# Zaq_ISO.net
KiCad netlist of a schematic drawn in EAGLE
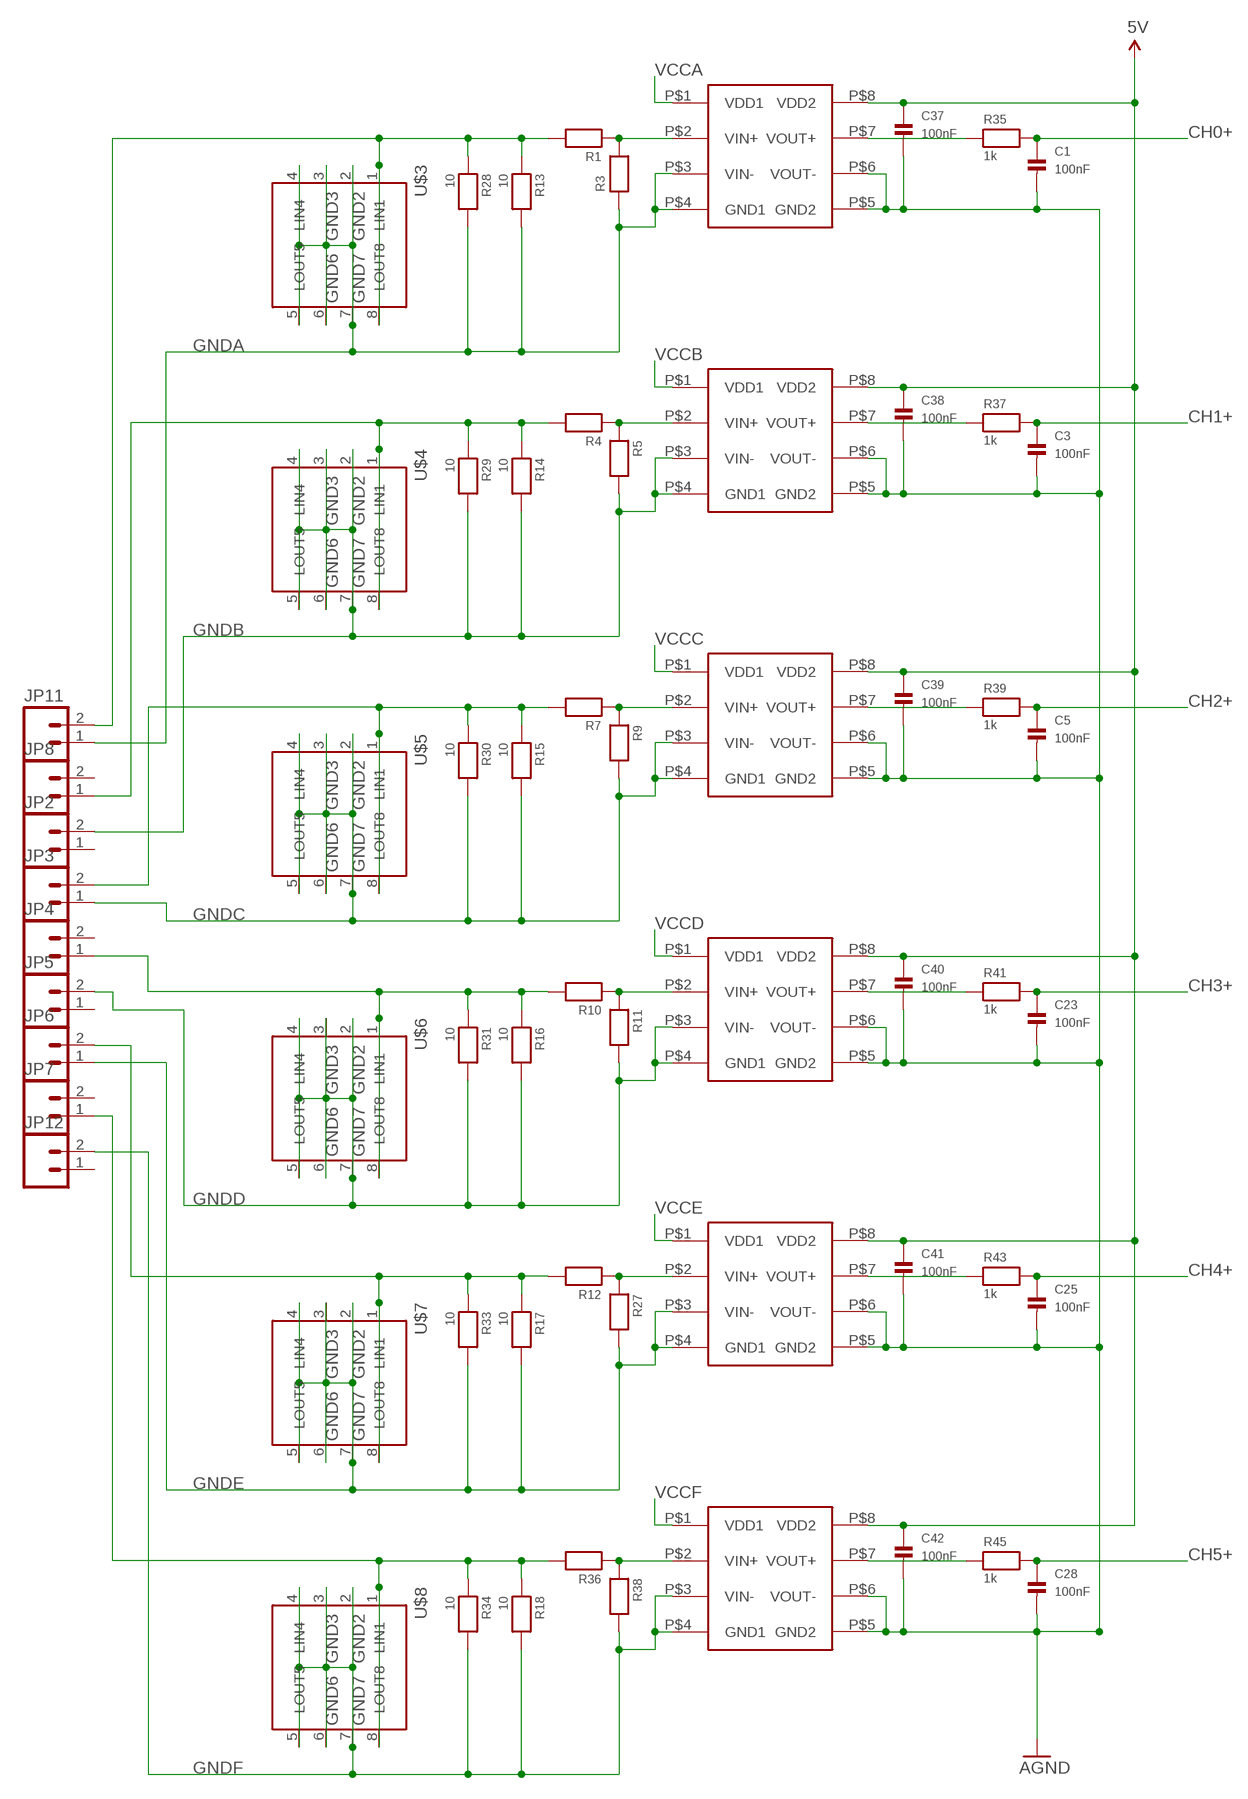
[diagram p0: schematic, sheet 1, part 1 of 2]
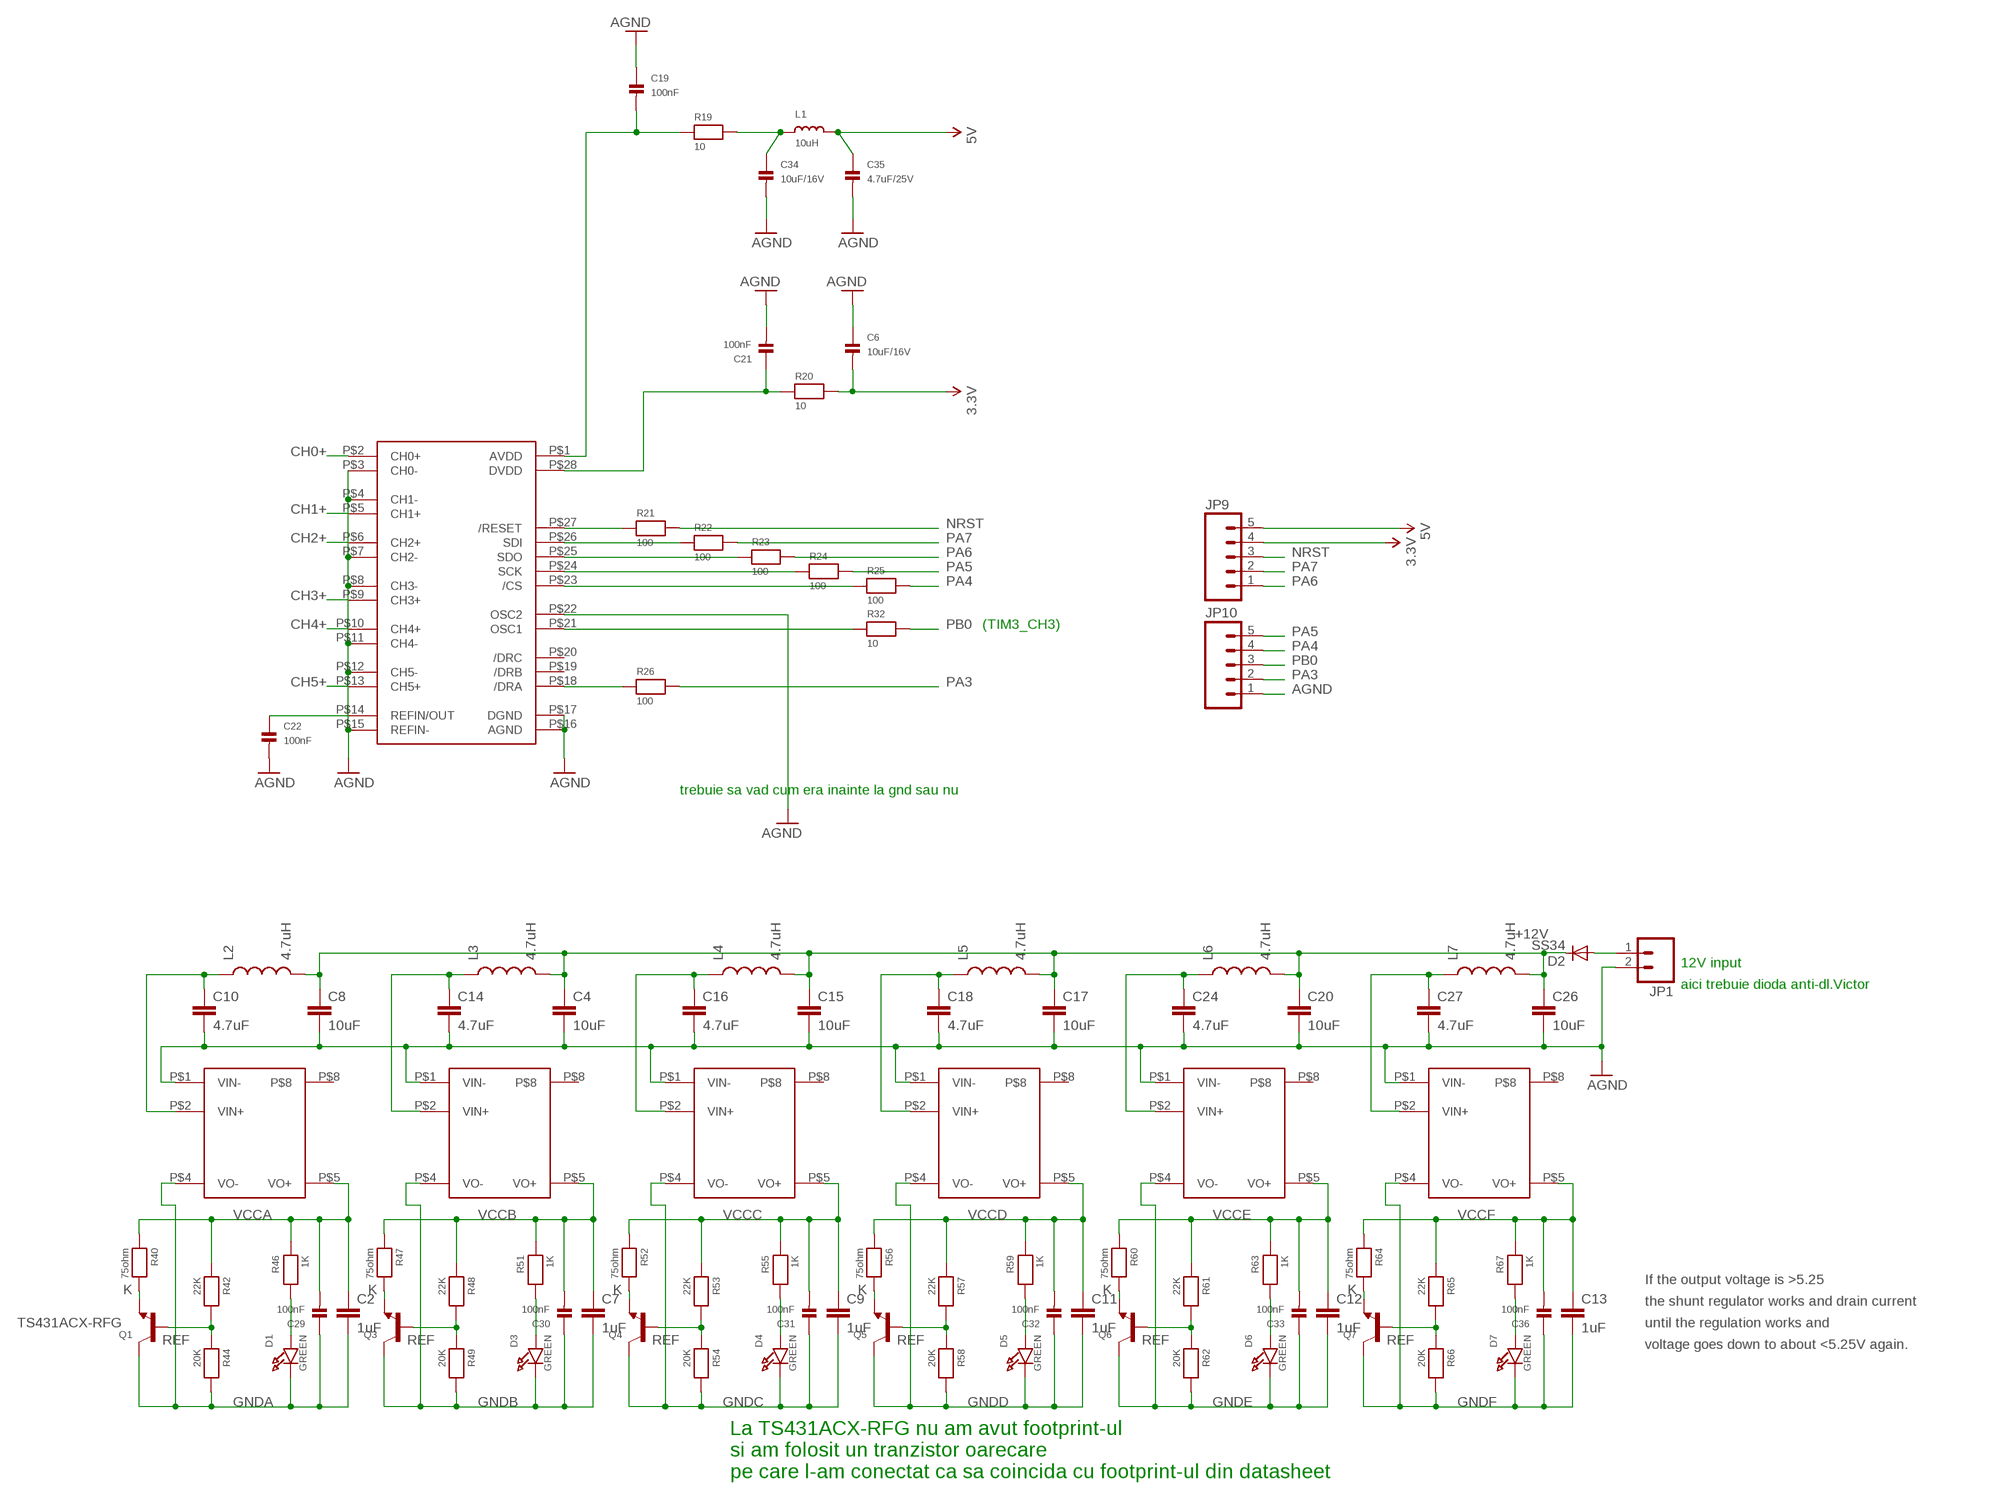
[diagram p1: schematic, sheet 1, part 2 of 2]

(export (version "E")
  (design (tool "Eeschema 10.0.6"))
  (components
    (comp (ref ".")
      (value "MCP3903")
      (footprint "eagle-import:SSOP-28")
      (libsource (lib "eagle-import") (part "MCP3903"))
    )
    (comp (ref "C1")
      (value "100nF")
      (footprint "eagle-import:_0805MP")
      (libsource (lib "eagle-import") (part "CAP_CERAMIC_0805MP"))
    )
    (comp (ref "C2")
      (value "1uF")
      (footprint "eagle-import:1206")
      (libsource (lib "eagle-import") (part "CAP1206"))
    )
    (comp (ref "C3")
      (value "100nF")
      (footprint "eagle-import:_0805MP")
      (libsource (lib "eagle-import") (part "CAP_CERAMIC_0805MP"))
    )
    (comp (ref "C4")
      (value "10uF")
      (footprint "eagle-import:1206")
      (libsource (lib "eagle-import") (part "CAP1206"))
    )
    (comp (ref "C5")
      (value "100nF")
      (footprint "eagle-import:_0805MP")
      (libsource (lib "eagle-import") (part "CAP_CERAMIC_0805MP"))
    )
    (comp (ref "C6")
      (value "10uF/16V")
      (footprint "eagle-import:_0805MP")
      (libsource (lib "eagle-import") (part "CAP_CERAMIC_0805MP"))
    )
    (comp (ref "C7")
      (value "1uF")
      (footprint "eagle-import:1206")
      (libsource (lib "eagle-import") (part "CAP1206"))
    )
    (comp (ref "C8")
      (value "10uF")
      (footprint "eagle-import:1206")
      (libsource (lib "eagle-import") (part "CAP1206"))
    )
    (comp (ref "C9")
      (value "1uF")
      (footprint "eagle-import:1206")
      (libsource (lib "eagle-import") (part "CAP1206"))
    )
    (comp (ref "C10")
      (value "4.7uF")
      (footprint "eagle-import:1206")
      (libsource (lib "eagle-import") (part "CAP1206"))
    )
    (comp (ref "C11")
      (value "1uF")
      (footprint "eagle-import:1206")
      (libsource (lib "eagle-import") (part "CAP1206"))
    )
    (comp (ref "C12")
      (value "1uF")
      (footprint "eagle-import:1206")
      (libsource (lib "eagle-import") (part "CAP1206"))
    )
    (comp (ref "C13")
      (value "1uF")
      (footprint "eagle-import:1206")
      (libsource (lib "eagle-import") (part "CAP1206"))
    )
    (comp (ref "C14")
      (value "4.7uF")
      (footprint "eagle-import:1206")
      (libsource (lib "eagle-import") (part "CAP1206"))
    )
    (comp (ref "C15")
      (value "10uF")
      (footprint "eagle-import:1206")
      (libsource (lib "eagle-import") (part "CAP1206"))
    )
    (comp (ref "C16")
      (value "4.7uF")
      (footprint "eagle-import:1206")
      (libsource (lib "eagle-import") (part "CAP1206"))
    )
    (comp (ref "C17")
      (value "10uF")
      (footprint "eagle-import:1206")
      (libsource (lib "eagle-import") (part "CAP1206"))
    )
    (comp (ref "C18")
      (value "4.7uF")
      (footprint "eagle-import:1206")
      (libsource (lib "eagle-import") (part "CAP1206"))
    )
    (comp (ref "C19")
      (value "100nF")
      (footprint "eagle-import:_0805MP")
      (libsource (lib "eagle-import") (part "CAP_CERAMIC_0805MP"))
    )
    (comp (ref "C20")
      (value "10uF")
      (footprint "eagle-import:1206")
      (libsource (lib "eagle-import") (part "CAP1206"))
    )
    (comp (ref "C21")
      (value "100nF")
      (footprint "eagle-import:_0805MP")
      (libsource (lib "eagle-import") (part "CAP_CERAMIC_0805MP"))
    )
    (comp (ref "C22")
      (value "100nF")
      (footprint "eagle-import:_0805MP")
      (libsource (lib "eagle-import") (part "CAP_CERAMIC_0805MP"))
    )
    (comp (ref "C23")
      (value "100nF")
      (footprint "eagle-import:_0805MP")
      (libsource (lib "eagle-import") (part "CAP_CERAMIC_0805MP"))
    )
    (comp (ref "C24")
      (value "4.7uF")
      (footprint "eagle-import:1206")
      (libsource (lib "eagle-import") (part "CAP1206"))
    )
    (comp (ref "C25")
      (value "100nF")
      (footprint "eagle-import:_0805MP")
      (libsource (lib "eagle-import") (part "CAP_CERAMIC_0805MP"))
    )
    (comp (ref "C26")
      (value "10uF")
      (footprint "eagle-import:1206")
      (libsource (lib "eagle-import") (part "CAP1206"))
    )
    (comp (ref "C27")
      (value "4.7uF")
      (footprint "eagle-import:1206")
      (libsource (lib "eagle-import") (part "CAP1206"))
    )
    (comp (ref "C28")
      (value "100nF")
      (footprint "eagle-import:_0805MP")
      (libsource (lib "eagle-import") (part "CAP_CERAMIC_0805MP"))
    )
    (comp (ref "C29")
      (value "100nF")
      (footprint "eagle-import:_0805MP")
      (libsource (lib "eagle-import") (part "CAP_CERAMIC_0805MP"))
    )
    (comp (ref "C30")
      (value "100nF")
      (footprint "eagle-import:_0805MP")
      (libsource (lib "eagle-import") (part "CAP_CERAMIC_0805MP"))
    )
    (comp (ref "C31")
      (value "100nF")
      (footprint "eagle-import:_0805MP")
      (libsource (lib "eagle-import") (part "CAP_CERAMIC_0805MP"))
    )
    (comp (ref "C32")
      (value "100nF")
      (footprint "eagle-import:_0805MP")
      (libsource (lib "eagle-import") (part "CAP_CERAMIC_0805MP"))
    )
    (comp (ref "C33")
      (value "100nF")
      (footprint "eagle-import:_0805MP")
      (libsource (lib "eagle-import") (part "CAP_CERAMIC_0805MP"))
    )
    (comp (ref "C34")
      (value "10uF/16V")
      (footprint "eagle-import:_0805MP")
      (libsource (lib "eagle-import") (part "CAP_CERAMIC_0805MP"))
    )
    (comp (ref "C35")
      (value "4.7uF/25V")
      (footprint "eagle-import:_0805MP")
      (libsource (lib "eagle-import") (part "CAP_CERAMIC_0805MP"))
    )
    (comp (ref "C36")
      (value "100nF")
      (footprint "eagle-import:_0805MP")
      (libsource (lib "eagle-import") (part "CAP_CERAMIC_0805MP"))
    )
    (comp (ref "C37")
      (value "100nF")
      (footprint "eagle-import:_0805MP")
      (libsource (lib "eagle-import") (part "CAP_CERAMIC_0805MP"))
    )
    (comp (ref "C38")
      (value "100nF")
      (footprint "eagle-import:_0805MP")
      (libsource (lib "eagle-import") (part "CAP_CERAMIC_0805MP"))
    )
    (comp (ref "C39")
      (value "100nF")
      (footprint "eagle-import:_0805MP")
      (libsource (lib "eagle-import") (part "CAP_CERAMIC_0805MP"))
    )
    (comp (ref "C40")
      (value "100nF")
      (footprint "eagle-import:_0805MP")
      (libsource (lib "eagle-import") (part "CAP_CERAMIC_0805MP"))
    )
    (comp (ref "C41")
      (value "100nF")
      (footprint "eagle-import:_0805MP")
      (libsource (lib "eagle-import") (part "CAP_CERAMIC_0805MP"))
    )
    (comp (ref "C42")
      (value "100nF")
      (footprint "eagle-import:_0805MP")
      (libsource (lib "eagle-import") (part "CAP_CERAMIC_0805MP"))
    )
    (comp (ref "D1")
      (value "GREEN")
      (footprint "eagle-import:CHIPLED_0805_NOOUTLINE")
      (libsource (lib "eagle-import") (part "LED0805_NOOUTLINE"))
    )
    (comp (ref "D2")
      (value "SS34")
      (footprint "eagle-import:SMC")
      (libsource (lib "eagle-import") (part "DIODE-SMC"))
    )
    (comp (ref "D3")
      (value "GREEN")
      (footprint "eagle-import:CHIPLED_0805_NOOUTLINE")
      (libsource (lib "eagle-import") (part "LED0805_NOOUTLINE"))
    )
    (comp (ref "D4")
      (value "GREEN")
      (footprint "eagle-import:CHIPLED_0805_NOOUTLINE")
      (libsource (lib "eagle-import") (part "LED0805_NOOUTLINE"))
    )
    (comp (ref "D5")
      (value "GREEN")
      (footprint "eagle-import:CHIPLED_0805_NOOUTLINE")
      (libsource (lib "eagle-import") (part "LED0805_NOOUTLINE"))
    )
    (comp (ref "D6")
      (value "GREEN")
      (footprint "eagle-import:CHIPLED_0805_NOOUTLINE")
      (libsource (lib "eagle-import") (part "LED0805_NOOUTLINE"))
    )
    (comp (ref "D7")
      (value "GREEN")
      (footprint "eagle-import:CHIPLED_0805_NOOUTLINE")
      (libsource (lib "eagle-import") (part "LED0805_NOOUTLINE"))
    )
    (comp (ref "JP1")
      (value "M025MM")
      (footprint "eagle-import:SCREWTERMINAL-5MM-2")
      (libsource (lib "eagle-import") (part "M025MM"))
    )
    (comp (ref "JP2")
      (value "M025MM")
      (footprint "eagle-import:SCREWTERMINAL-5MM-2")
      (libsource (lib "eagle-import") (part "M025MM"))
    )
    (comp (ref "JP3")
      (value "M025MM")
      (footprint "eagle-import:SCREWTERMINAL-5MM-2")
      (libsource (lib "eagle-import") (part "M025MM"))
    )
    (comp (ref "JP4")
      (value "M025MM")
      (footprint "eagle-import:SCREWTERMINAL-5MM-2")
      (libsource (lib "eagle-import") (part "M025MM"))
    )
    (comp (ref "JP5")
      (value "M025MM")
      (footprint "eagle-import:SCREWTERMINAL-5MM-2")
      (libsource (lib "eagle-import") (part "M025MM"))
    )
    (comp (ref "JP6")
      (value "M025MM")
      (footprint "eagle-import:SCREWTERMINAL-5MM-2")
      (libsource (lib "eagle-import") (part "M025MM"))
    )
    (comp (ref "JP7")
      (value "M025MM")
      (footprint "eagle-import:SCREWTERMINAL-5MM-2")
      (libsource (lib "eagle-import") (part "M025MM"))
    )
    (comp (ref "JP8")
      (value "M025MM")
      (footprint "eagle-import:SCREWTERMINAL-5MM-2")
      (libsource (lib "eagle-import") (part "M025MM"))
    )
    (comp (ref "JP9")
      (value "M05PTH_LONGPADS")
      (footprint "eagle-import:1X05_LONGPADS")
      (libsource (lib "eagle-import") (part "M05PTH_LONGPADS"))
    )
    (comp (ref "JP10")
      (value "M05PTH_LONGPADS")
      (footprint "eagle-import:1X05_LONGPADS")
      (libsource (lib "eagle-import") (part "M05PTH_LONGPADS"))
    )
    (comp (ref "JP11")
      (value "M025MM")
      (footprint "eagle-import:SCREWTERMINAL-5MM-2")
      (libsource (lib "eagle-import") (part "M025MM"))
    )
    (comp (ref "JP12")
      (value "M025MM")
      (footprint "eagle-import:SCREWTERMINAL-5MM-2")
      (libsource (lib "eagle-import") (part "M025MM"))
    )
    (comp (ref "L1")
      (value "10uH")
      (footprint "eagle-import:_0805MP")
      (libsource (lib "eagle-import") (part "INDUCTOR_0805MP"))
    )
    (comp (ref "L2")
      (value "4.7uH")
      (footprint "eagle-import:1210")
      (libsource (lib "eagle-import") (part "INDUCTOR1210"))
    )
    (comp (ref "L3")
      (value "4.7uH")
      (footprint "eagle-import:1210")
      (libsource (lib "eagle-import") (part "INDUCTOR1210"))
    )
    (comp (ref "L4")
      (value "4.7uH")
      (footprint "eagle-import:1210")
      (libsource (lib "eagle-import") (part "INDUCTOR1210"))
    )
    (comp (ref "L5")
      (value "4.7uH")
      (footprint "eagle-import:1210")
      (libsource (lib "eagle-import") (part "INDUCTOR1210"))
    )
    (comp (ref "L6")
      (value "4.7uH")
      (footprint "eagle-import:1210")
      (libsource (lib "eagle-import") (part "INDUCTOR1210"))
    )
    (comp (ref "L7")
      (value "4.7uH")
      (footprint "eagle-import:1210")
      (libsource (lib "eagle-import") (part "INDUCTOR1210"))
    )
    (comp (ref "Q1")
      (value "TRANSISTOR_NPNWAVE")
      (footprint "eagle-import:SOT23-W")
      (libsource (lib "eagle-import") (part "TRANSISTOR_NPNWAVE"))
    )
    (comp (ref "Q3")
      (value "TRANSISTOR_NPNWAVE")
      (footprint "eagle-import:SOT23-W")
      (libsource (lib "eagle-import") (part "TRANSISTOR_NPNWAVE"))
    )
    (comp (ref "Q4")
      (value "TRANSISTOR_NPNWAVE")
      (footprint "eagle-import:SOT23-W")
      (libsource (lib "eagle-import") (part "TRANSISTOR_NPNWAVE"))
    )
    (comp (ref "Q5")
      (value "TRANSISTOR_NPNWAVE")
      (footprint "eagle-import:SOT23-W")
      (libsource (lib "eagle-import") (part "TRANSISTOR_NPNWAVE"))
    )
    (comp (ref "Q6")
      (value "TRANSISTOR_NPNWAVE")
      (footprint "eagle-import:SOT23-W")
      (libsource (lib "eagle-import") (part "TRANSISTOR_NPNWAVE"))
    )
    (comp (ref "Q7")
      (value "TRANSISTOR_NPNWAVE")
      (footprint "eagle-import:SOT23-W")
      (libsource (lib "eagle-import") (part "TRANSISTOR_NPNWAVE"))
    )
    (comp (ref "R1")
      (value "RESISTOR_0805MP")
      (footprint "eagle-import:_0805MP")
      (libsource (lib "eagle-import") (part "RESISTOR_0805MP"))
    )
    (comp (ref "R3")
      (value "RESISTOR_0805MP")
      (footprint "eagle-import:_0805MP")
      (libsource (lib "eagle-import") (part "RESISTOR_0805MP"))
    )
    (comp (ref "R4")
      (value "RESISTOR_0805MP")
      (footprint "eagle-import:_0805MP")
      (libsource (lib "eagle-import") (part "RESISTOR_0805MP"))
    )
    (comp (ref "R5")
      (value "RESISTOR_0805MP")
      (footprint "eagle-import:_0805MP")
      (libsource (lib "eagle-import") (part "RESISTOR_0805MP"))
    )
    (comp (ref "R7")
      (value "RESISTOR_0805MP")
      (footprint "eagle-import:_0805MP")
      (libsource (lib "eagle-import") (part "RESISTOR_0805MP"))
    )
    (comp (ref "R9")
      (value "RESISTOR_0805MP")
      (footprint "eagle-import:_0805MP")
      (libsource (lib "eagle-import") (part "RESISTOR_0805MP"))
    )
    (comp (ref "R10")
      (value "RESISTOR_0805MP")
      (footprint "eagle-import:_0805MP")
      (libsource (lib "eagle-import") (part "RESISTOR_0805MP"))
    )
    (comp (ref "R11")
      (value "RESISTOR_0805MP")
      (footprint "eagle-import:_0805MP")
      (libsource (lib "eagle-import") (part "RESISTOR_0805MP"))
    )
    (comp (ref "R12")
      (value "RESISTOR_0805MP")
      (footprint "eagle-import:_0805MP")
      (libsource (lib "eagle-import") (part "RESISTOR_0805MP"))
    )
    (comp (ref "R13")
      (value "10")
      (footprint "eagle-import:1206")
      (libsource (lib "eagle-import") (part "RESISTOR1206"))
    )
    (comp (ref "R14")
      (value "10")
      (footprint "eagle-import:1206")
      (libsource (lib "eagle-import") (part "RESISTOR1206"))
    )
    (comp (ref "R15")
      (value "10")
      (footprint "eagle-import:1206")
      (libsource (lib "eagle-import") (part "RESISTOR1206"))
    )
    (comp (ref "R16")
      (value "10")
      (footprint "eagle-import:1206")
      (libsource (lib "eagle-import") (part "RESISTOR1206"))
    )
    (comp (ref "R17")
      (value "10")
      (footprint "eagle-import:1206")
      (libsource (lib "eagle-import") (part "RESISTOR1206"))
    )
    (comp (ref "R18")
      (value "10")
      (footprint "eagle-import:1206")
      (libsource (lib "eagle-import") (part "RESISTOR1206"))
    )
    (comp (ref "R19")
      (value "10")
      (footprint "eagle-import:_0805MP")
      (libsource (lib "eagle-import") (part "RESISTOR_0805MP"))
    )
    (comp (ref "R20")
      (value "10")
      (footprint "eagle-import:_0805MP")
      (libsource (lib "eagle-import") (part "RESISTOR_0805MP"))
    )
    (comp (ref "R21")
      (value "100")
      (footprint "eagle-import:_0805MP")
      (libsource (lib "eagle-import") (part "RESISTOR_0805MP"))
    )
    (comp (ref "R22")
      (value "100")
      (footprint "eagle-import:_0805MP")
      (libsource (lib "eagle-import") (part "RESISTOR_0805MP"))
    )
    (comp (ref "R23")
      (value "100")
      (footprint "eagle-import:_0805MP")
      (libsource (lib "eagle-import") (part "RESISTOR_0805MP"))
    )
    (comp (ref "R24")
      (value "100")
      (footprint "eagle-import:_0805MP")
      (libsource (lib "eagle-import") (part "RESISTOR_0805MP"))
    )
    (comp (ref "R25")
      (value "100")
      (footprint "eagle-import:_0805MP")
      (libsource (lib "eagle-import") (part "RESISTOR_0805MP"))
    )
    (comp (ref "R26")
      (value "100")
      (footprint "eagle-import:_0805MP")
      (libsource (lib "eagle-import") (part "RESISTOR_0805MP"))
    )
    (comp (ref "R27")
      (value "RESISTOR_0805MP")
      (footprint "eagle-import:_0805MP")
      (libsource (lib "eagle-import") (part "RESISTOR_0805MP"))
    )
    (comp (ref "R28")
      (value "10")
      (footprint "eagle-import:1206")
      (libsource (lib "eagle-import") (part "RESISTOR1206"))
    )
    (comp (ref "R29")
      (value "10")
      (footprint "eagle-import:1206")
      (libsource (lib "eagle-import") (part "RESISTOR1206"))
    )
    (comp (ref "R30")
      (value "10")
      (footprint "eagle-import:1206")
      (libsource (lib "eagle-import") (part "RESISTOR1206"))
    )
    (comp (ref "R31")
      (value "10")
      (footprint "eagle-import:1206")
      (libsource (lib "eagle-import") (part "RESISTOR1206"))
    )
    (comp (ref "R32")
      (value "10")
      (footprint "eagle-import:_0805MP")
      (libsource (lib "eagle-import") (part "RESISTOR_0805MP"))
    )
    (comp (ref "R33")
      (value "10")
      (footprint "eagle-import:1206")
      (libsource (lib "eagle-import") (part "RESISTOR1206"))
    )
    (comp (ref "R34")
      (value "10")
      (footprint "eagle-import:1206")
      (libsource (lib "eagle-import") (part "RESISTOR1206"))
    )
    (comp (ref "R35")
      (value "1k")
      (footprint "eagle-import:_0805MP")
      (libsource (lib "eagle-import") (part "RESISTOR_0805MP"))
    )
    (comp (ref "R36")
      (value "RESISTOR_0805MP")
      (footprint "eagle-import:_0805MP")
      (libsource (lib "eagle-import") (part "RESISTOR_0805MP"))
    )
    (comp (ref "R37")
      (value "1k")
      (footprint "eagle-import:_0805MP")
      (libsource (lib "eagle-import") (part "RESISTOR_0805MP"))
    )
    (comp (ref "R38")
      (value "RESISTOR_0805MP")
      (footprint "eagle-import:_0805MP")
      (libsource (lib "eagle-import") (part "RESISTOR_0805MP"))
    )
    (comp (ref "R39")
      (value "1k")
      (footprint "eagle-import:_0805MP")
      (libsource (lib "eagle-import") (part "RESISTOR_0805MP"))
    )
    (comp (ref "R40")
      (value "75ohm")
      (footprint "eagle-import:_0805MP")
      (libsource (lib "eagle-import") (part "RESISTOR_0805MP"))
    )
    (comp (ref "R41")
      (value "1k")
      (footprint "eagle-import:_0805MP")
      (libsource (lib "eagle-import") (part "RESISTOR_0805MP"))
    )
    (comp (ref "R42")
      (value "22K")
      (footprint "eagle-import:_0805MP")
      (libsource (lib "eagle-import") (part "RESISTOR_0805MP"))
    )
    (comp (ref "R43")
      (value "1k")
      (footprint "eagle-import:_0805MP")
      (libsource (lib "eagle-import") (part "RESISTOR_0805MP"))
    )
    (comp (ref "R44")
      (value "20K")
      (footprint "eagle-import:_0805MP")
      (libsource (lib "eagle-import") (part "RESISTOR_0805MP"))
    )
    (comp (ref "R45")
      (value "1k")
      (footprint "eagle-import:_0805MP")
      (libsource (lib "eagle-import") (part "RESISTOR_0805MP"))
    )
    (comp (ref "R46")
      (value "1K")
      (footprint "eagle-import:_0805MP")
      (libsource (lib "eagle-import") (part "RESISTOR_0805MP"))
    )
    (comp (ref "R47")
      (value "75ohm")
      (footprint "eagle-import:_0805MP")
      (libsource (lib "eagle-import") (part "RESISTOR_0805MP"))
    )
    (comp (ref "R48")
      (value "22K")
      (footprint "eagle-import:_0805MP")
      (libsource (lib "eagle-import") (part "RESISTOR_0805MP"))
    )
    (comp (ref "R49")
      (value "20K")
      (footprint "eagle-import:_0805MP")
      (libsource (lib "eagle-import") (part "RESISTOR_0805MP"))
    )
    (comp (ref "R51")
      (value "1K")
      (footprint "eagle-import:_0805MP")
      (libsource (lib "eagle-import") (part "RESISTOR_0805MP"))
    )
    (comp (ref "R52")
      (value "75ohm")
      (footprint "eagle-import:_0805MP")
      (libsource (lib "eagle-import") (part "RESISTOR_0805MP"))
    )
    (comp (ref "R53")
      (value "22K")
      (footprint "eagle-import:_0805MP")
      (libsource (lib "eagle-import") (part "RESISTOR_0805MP"))
    )
    (comp (ref "R54")
      (value "20K")
      (footprint "eagle-import:_0805MP")
      (libsource (lib "eagle-import") (part "RESISTOR_0805MP"))
    )
    (comp (ref "R55")
      (value "1K")
      (footprint "eagle-import:_0805MP")
      (libsource (lib "eagle-import") (part "RESISTOR_0805MP"))
    )
    (comp (ref "R56")
      (value "75ohm")
      (footprint "eagle-import:_0805MP")
      (libsource (lib "eagle-import") (part "RESISTOR_0805MP"))
    )
    (comp (ref "R57")
      (value "22K")
      (footprint "eagle-import:_0805MP")
      (libsource (lib "eagle-import") (part "RESISTOR_0805MP"))
    )
    (comp (ref "R58")
      (value "20K")
      (footprint "eagle-import:_0805MP")
      (libsource (lib "eagle-import") (part "RESISTOR_0805MP"))
    )
    (comp (ref "R59")
      (value "1K")
      (footprint "eagle-import:_0805MP")
      (libsource (lib "eagle-import") (part "RESISTOR_0805MP"))
    )
    (comp (ref "R60")
      (value "75ohm")
      (footprint "eagle-import:_0805MP")
      (libsource (lib "eagle-import") (part "RESISTOR_0805MP"))
    )
    (comp (ref "R61")
      (value "22K")
      (footprint "eagle-import:_0805MP")
      (libsource (lib "eagle-import") (part "RESISTOR_0805MP"))
    )
    (comp (ref "R62")
      (value "20K")
      (footprint "eagle-import:_0805MP")
      (libsource (lib "eagle-import") (part "RESISTOR_0805MP"))
    )
    (comp (ref "R63")
      (value "1K")
      (footprint "eagle-import:_0805MP")
      (libsource (lib "eagle-import") (part "RESISTOR_0805MP"))
    )
    (comp (ref "R64")
      (value "75ohm")
      (footprint "eagle-import:_0805MP")
      (libsource (lib "eagle-import") (part "RESISTOR_0805MP"))
    )
    (comp (ref "R65")
      (value "22K")
      (footprint "eagle-import:_0805MP")
      (libsource (lib "eagle-import") (part "RESISTOR_0805MP"))
    )
    (comp (ref "R66")
      (value "20K")
      (footprint "eagle-import:_0805MP")
      (libsource (lib "eagle-import") (part "RESISTOR_0805MP"))
    )
    (comp (ref "R67")
      (value "1K")
      (footprint "eagle-import:_0805MP")
      (libsource (lib "eagle-import") (part "RESISTOR_0805MP"))
    )
    (comp (ref "U$2")
      (value "AMC1200SDUB")
      (footprint "eagle-import:SOP")
      (libsource (lib "eagle-import") (part "AMC1200SDUB"))
    )
    (comp (ref "U$3")
      (value "LC03_3V3")
      (footprint "eagle-import:SO8")
      (libsource (lib "eagle-import") (part "LC03_3V3"))
    )
    (comp (ref "U$4")
      (value "LC03_3V3")
      (footprint "eagle-import:SO8")
      (libsource (lib "eagle-import") (part "LC03_3V3"))
    )
    (comp (ref "U$5")
      (value "LC03_3V3")
      (footprint "eagle-import:SO8")
      (libsource (lib "eagle-import") (part "LC03_3V3"))
    )
    (comp (ref "U$6")
      (value "LC03_3V3")
      (footprint "eagle-import:SO8")
      (libsource (lib "eagle-import") (part "LC03_3V3"))
    )
    (comp (ref "U$7")
      (value "LC03_3V3")
      (footprint "eagle-import:SO8")
      (libsource (lib "eagle-import") (part "LC03_3V3"))
    )
    (comp (ref "U$8")
      (value "LC03_3V3")
      (footprint "eagle-import:SO8")
      (libsource (lib "eagle-import") (part "LC03_3V3"))
    )
    (comp (ref "U$9")
      (value "AMC1200SDUB")
      (footprint "eagle-import:SOP")
      (libsource (lib "eagle-import") (part "AMC1200SDUB"))
    )
    (comp (ref "U$12")
      (value "AMC1200SDUB")
      (footprint "eagle-import:SOP")
      (libsource (lib "eagle-import") (part "AMC1200SDUB"))
    )
    (comp (ref "U$16")
      (value "AMC1200SDUB")
      (footprint "eagle-import:SOP")
      (libsource (lib "eagle-import") (part "AMC1200SDUB"))
    )
    (comp (ref "U$17")
      (value "AM1LS-NJZ")
      (footprint "eagle-import:AM1LS-JZ")
      (libsource (lib "eagle-import") (part "AM1LS-NJZ"))
    )
    (comp (ref "U$18")
      (value "AMC1200SDUB")
      (footprint "eagle-import:SOP")
      (libsource (lib "eagle-import") (part "AMC1200SDUB"))
    )
    (comp (ref "U$19")
      (value "AMC1200SDUB")
      (footprint "eagle-import:SOP")
      (libsource (lib "eagle-import") (part "AMC1200SDUB"))
    )
    (comp (ref "U$20")
      (value "AM1LS-NJZ")
      (footprint "eagle-import:AM1LS-JZ")
      (libsource (lib "eagle-import") (part "AM1LS-NJZ"))
    )
    (comp (ref "U$22")
      (value "AM1LS-NJZ")
      (footprint "eagle-import:AM1LS-JZ")
      (libsource (lib "eagle-import") (part "AM1LS-NJZ"))
    )
    (comp (ref "U$23")
      (value "AM1LS-NJZ")
      (footprint "eagle-import:AM1LS-JZ")
      (libsource (lib "eagle-import") (part "AM1LS-NJZ"))
    )
    (comp (ref "U$24")
      (value "AM1LS-NJZ")
      (footprint "eagle-import:AM1LS-JZ")
      (libsource (lib "eagle-import") (part "AM1LS-NJZ"))
    )
    (comp (ref "U$25")
      (value "AM1LS-NJZ")
      (footprint "eagle-import:AM1LS-JZ")
      (libsource (lib "eagle-import") (part "AM1LS-NJZ"))
    )
  )
  (nets
    (net (code "1") (name "/+12V") (class "Default")
      (node (ref "C15") (pin "1") (pinfunction "1_1") (pintype "passive"))
      (node (ref "C17") (pin "1") (pinfunction "1_1") (pintype "passive"))
      (node (ref "C20") (pin "1") (pinfunction "1_1") (pintype "passive"))
      (node (ref "C26") (pin "1") (pinfunction "1_1") (pintype "passive"))
      (node (ref "C4") (pin "1") (pinfunction "1_1") (pintype "passive"))
      (node (ref "C8") (pin "1") (pinfunction "1_1") (pintype "passive"))
      (node (ref "D2") (pin "C") (pinfunction "C_C") (pintype "passive"))
      (node (ref "L2") (pin "2") (pinfunction "2_2") (pintype "passive"))
      (node (ref "L3") (pin "2") (pinfunction "2_2") (pintype "passive"))
      (node (ref "L4") (pin "2") (pinfunction "2_2") (pintype "passive"))
      (node (ref "L5") (pin "2") (pinfunction "2_2") (pintype "passive"))
      (node (ref "L6") (pin "2") (pinfunction "2_2") (pintype "passive"))
      (node (ref "L7") (pin "2") (pinfunction "2_2") (pintype "passive"))
    )
    (net (code "2") (name "/CH0+") (class "Default")
      (node (ref ".") (pin "P$2") (pinfunction "CH0+_P$2") (pintype "bidirectional"))
      (node (ref "C1") (pin "1") (pinfunction "P$1_1") (pintype "passive"))
      (node (ref "R35") (pin "2") (pinfunction "2_2") (pintype "passive"))
    )
    (net (code "3") (name "/CH1+") (class "Default")
      (node (ref ".") (pin "P$5") (pinfunction "CH1+_P$5") (pintype "bidirectional"))
      (node (ref "C3") (pin "1") (pinfunction "P$1_1") (pintype "passive"))
      (node (ref "R37") (pin "2") (pinfunction "2_2") (pintype "passive"))
    )
    (net (code "4") (name "/CH2+") (class "Default")
      (node (ref ".") (pin "P$6") (pinfunction "CH2+_P$6") (pintype "bidirectional"))
      (node (ref "C5") (pin "1") (pinfunction "P$1_1") (pintype "passive"))
      (node (ref "R39") (pin "2") (pinfunction "2_2") (pintype "passive"))
    )
    (net (code "5") (name "/CH3+") (class "Default")
      (node (ref ".") (pin "P$9") (pinfunction "CH3+_P$9") (pintype "bidirectional"))
      (node (ref "C23") (pin "1") (pinfunction "P$1_1") (pintype "passive"))
      (node (ref "R41") (pin "2") (pinfunction "2_2") (pintype "passive"))
    )
    (net (code "6") (name "/CH4+") (class "Default")
      (node (ref ".") (pin "P$10") (pinfunction "CH4+_P$10") (pintype "bidirectional"))
      (node (ref "C25") (pin "1") (pinfunction "P$1_1") (pintype "passive"))
      (node (ref "R43") (pin "2") (pinfunction "2_2") (pintype "passive"))
    )
    (net (code "7") (name "/CH5+") (class "Default")
      (node (ref ".") (pin "P$13") (pinfunction "CH5+_P$13") (pintype "bidirectional"))
      (node (ref "C28") (pin "1") (pinfunction "P$1_1") (pintype "passive"))
      (node (ref "R45") (pin "2") (pinfunction "2_2") (pintype "passive"))
    )
    (net (code "8") (name "/GNDA") (class "Default")
      (node (ref "C2") (pin "2") (pinfunction "2_2") (pintype "passive"))
      (node (ref "C29") (pin "1") (pinfunction "P$1_1") (pintype "passive"))
      (node (ref "D1") (pin "C") (pinfunction "C_C") (pintype "passive"))
      (node (ref "JP11") (pin "1") (pinfunction "1_1") (pintype "passive"))
      (node (ref "Q1") (pin "3") (pinfunction "C_3") (pintype "passive"))
      (node (ref "R13") (pin "2") (pinfunction "2_2") (pintype "passive"))
      (node (ref "R28") (pin "2") (pinfunction "2_2") (pintype "passive"))
      (node (ref "R3") (pin "1") (pinfunction "1_1") (pintype "passive"))
      (node (ref "R44") (pin "2") (pinfunction "2_2") (pintype "passive"))
      (node (ref "U$17") (pin "P$4") (pinfunction "VO-_P$4") (pintype "power_in"))
      (node (ref "U$2") (pin "P$3") (pinfunction "VIN-_P$3") (pintype "bidirectional"))
      (node (ref "U$2") (pin "P$4") (pinfunction "GND1_P$4") (pintype "power_in"))
      (node (ref "U$3") (pin "2") (pinfunction "GND_2_2") (pintype "power_in"))
      (node (ref "U$3") (pin "3") (pinfunction "GND_3_3") (pintype "power_in"))
      (node (ref "U$3") (pin "4") (pinfunction "LIN4_4") (pintype "input"))
      (node (ref "U$3") (pin "5") (pinfunction "LOUT5_5") (pintype "input"))
      (node (ref "U$3") (pin "6") (pinfunction "GND_6_6") (pintype "power_in"))
      (node (ref "U$3") (pin "7") (pinfunction "GND_7_7") (pintype "power_in"))
    )
    (net (code "9") (name "/GNDB") (class "Default")
      (node (ref "C30") (pin "1") (pinfunction "P$1_1") (pintype "passive"))
      (node (ref "C7") (pin "2") (pinfunction "2_2") (pintype "passive"))
      (node (ref "D3") (pin "C") (pinfunction "C_C") (pintype "passive"))
      (node (ref "JP2") (pin "2") (pinfunction "2_2") (pintype "passive"))
      (node (ref "Q3") (pin "3") (pinfunction "C_3") (pintype "passive"))
      (node (ref "R14") (pin "2") (pinfunction "2_2") (pintype "passive"))
      (node (ref "R29") (pin "2") (pinfunction "2_2") (pintype "passive"))
      (node (ref "R49") (pin "2") (pinfunction "2_2") (pintype "passive"))
      (node (ref "R5") (pin "2") (pinfunction "2_2") (pintype "passive"))
      (node (ref "U$20") (pin "P$4") (pinfunction "VO-_P$4") (pintype "power_in"))
      (node (ref "U$4") (pin "2") (pinfunction "GND_2_2") (pintype "power_in"))
      (node (ref "U$4") (pin "3") (pinfunction "GND_3_3") (pintype "power_in"))
      (node (ref "U$4") (pin "4") (pinfunction "LIN4_4") (pintype "input"))
      (node (ref "U$4") (pin "5") (pinfunction "LOUT5_5") (pintype "input"))
      (node (ref "U$4") (pin "6") (pinfunction "GND_6_6") (pintype "power_in"))
      (node (ref "U$4") (pin "7") (pinfunction "GND_7_7") (pintype "power_in"))
      (node (ref "U$9") (pin "P$3") (pinfunction "VIN-_P$3") (pintype "bidirectional"))
      (node (ref "U$9") (pin "P$4") (pinfunction "GND1_P$4") (pintype "power_in"))
    )
    (net (code "10") (name "/GNDC") (class "Default")
      (node (ref "C31") (pin "1") (pinfunction "P$1_1") (pintype "passive"))
      (node (ref "C9") (pin "2") (pinfunction "2_2") (pintype "passive"))
      (node (ref "D4") (pin "C") (pinfunction "C_C") (pintype "passive"))
      (node (ref "JP3") (pin "1") (pinfunction "1_1") (pintype "passive"))
      (node (ref "Q4") (pin "3") (pinfunction "C_3") (pintype "passive"))
      (node (ref "R15") (pin "2") (pinfunction "2_2") (pintype "passive"))
      (node (ref "R30") (pin "2") (pinfunction "2_2") (pintype "passive"))
      (node (ref "R54") (pin "2") (pinfunction "2_2") (pintype "passive"))
      (node (ref "R9") (pin "2") (pinfunction "2_2") (pintype "passive"))
      (node (ref "U$12") (pin "P$3") (pinfunction "VIN-_P$3") (pintype "bidirectional"))
      (node (ref "U$12") (pin "P$4") (pinfunction "GND1_P$4") (pintype "power_in"))
      (node (ref "U$22") (pin "P$4") (pinfunction "VO-_P$4") (pintype "power_in"))
      (node (ref "U$5") (pin "2") (pinfunction "GND_2_2") (pintype "power_in"))
      (node (ref "U$5") (pin "3") (pinfunction "GND_3_3") (pintype "power_in"))
      (node (ref "U$5") (pin "4") (pinfunction "LIN4_4") (pintype "input"))
      (node (ref "U$5") (pin "5") (pinfunction "LOUT5_5") (pintype "input"))
      (node (ref "U$5") (pin "6") (pinfunction "GND_6_6") (pintype "power_in"))
      (node (ref "U$5") (pin "7") (pinfunction "GND_7_7") (pintype "power_in"))
    )
    (net (code "11") (name "/GNDD") (class "Default")
      (node (ref "C11") (pin "2") (pinfunction "2_2") (pintype "passive"))
      (node (ref "C32") (pin "1") (pinfunction "P$1_1") (pintype "passive"))
      (node (ref "D5") (pin "C") (pinfunction "C_C") (pintype "passive"))
      (node (ref "JP5") (pin "2") (pinfunction "2_2") (pintype "passive"))
      (node (ref "Q5") (pin "3") (pinfunction "C_3") (pintype "passive"))
      (node (ref "R11") (pin "2") (pinfunction "2_2") (pintype "passive"))
      (node (ref "R16") (pin "2") (pinfunction "2_2") (pintype "passive"))
      (node (ref "R31") (pin "2") (pinfunction "2_2") (pintype "passive"))
      (node (ref "R58") (pin "2") (pinfunction "2_2") (pintype "passive"))
      (node (ref "U$16") (pin "P$3") (pinfunction "VIN-_P$3") (pintype "bidirectional"))
      (node (ref "U$16") (pin "P$4") (pinfunction "GND1_P$4") (pintype "power_in"))
      (node (ref "U$23") (pin "P$4") (pinfunction "VO-_P$4") (pintype "power_in"))
      (node (ref "U$6") (pin "2") (pinfunction "GND_2_2") (pintype "power_in"))
      (node (ref "U$6") (pin "3") (pinfunction "GND_3_3") (pintype "power_in"))
      (node (ref "U$6") (pin "4") (pinfunction "LIN4_4") (pintype "input"))
      (node (ref "U$6") (pin "5") (pinfunction "LOUT5_5") (pintype "input"))
      (node (ref "U$6") (pin "6") (pinfunction "GND_6_6") (pintype "power_in"))
      (node (ref "U$6") (pin "7") (pinfunction "GND_7_7") (pintype "power_in"))
    )
    (net (code "12") (name "/GNDE") (class "Default")
      (node (ref "C12") (pin "2") (pinfunction "2_2") (pintype "passive"))
      (node (ref "C33") (pin "1") (pinfunction "P$1_1") (pintype "passive"))
      (node (ref "D6") (pin "C") (pinfunction "C_C") (pintype "passive"))
      (node (ref "JP6") (pin "1") (pinfunction "1_1") (pintype "passive"))
      (node (ref "Q6") (pin "3") (pinfunction "C_3") (pintype "passive"))
      (node (ref "R17") (pin "2") (pinfunction "2_2") (pintype "passive"))
      (node (ref "R27") (pin "2") (pinfunction "2_2") (pintype "passive"))
      (node (ref "R33") (pin "2") (pinfunction "2_2") (pintype "passive"))
      (node (ref "R62") (pin "2") (pinfunction "2_2") (pintype "passive"))
      (node (ref "U$18") (pin "P$3") (pinfunction "VIN-_P$3") (pintype "bidirectional"))
      (node (ref "U$18") (pin "P$4") (pinfunction "GND1_P$4") (pintype "power_in"))
      (node (ref "U$24") (pin "P$4") (pinfunction "VO-_P$4") (pintype "power_in"))
      (node (ref "U$7") (pin "2") (pinfunction "GND_2_2") (pintype "power_in"))
      (node (ref "U$7") (pin "3") (pinfunction "GND_3_3") (pintype "power_in"))
      (node (ref "U$7") (pin "4") (pinfunction "LIN4_4") (pintype "input"))
      (node (ref "U$7") (pin "5") (pinfunction "LOUT5_5") (pintype "input"))
      (node (ref "U$7") (pin "6") (pinfunction "GND_6_6") (pintype "power_in"))
      (node (ref "U$7") (pin "7") (pinfunction "GND_7_7") (pintype "power_in"))
    )
    (net (code "13") (name "/GNDF") (class "Default")
      (node (ref "C13") (pin "2") (pinfunction "2_2") (pintype "passive"))
      (node (ref "C36") (pin "1") (pinfunction "P$1_1") (pintype "passive"))
      (node (ref "D7") (pin "C") (pinfunction "C_C") (pintype "passive"))
      (node (ref "JP12") (pin "2") (pinfunction "2_2") (pintype "passive"))
      (node (ref "Q7") (pin "3") (pinfunction "C_3") (pintype "passive"))
      (node (ref "R18") (pin "2") (pinfunction "2_2") (pintype "passive"))
      (node (ref "R34") (pin "2") (pinfunction "2_2") (pintype "passive"))
      (node (ref "R38") (pin "2") (pinfunction "2_2") (pintype "passive"))
      (node (ref "R66") (pin "2") (pinfunction "2_2") (pintype "passive"))
      (node (ref "U$19") (pin "P$3") (pinfunction "VIN-_P$3") (pintype "bidirectional"))
      (node (ref "U$19") (pin "P$4") (pinfunction "GND1_P$4") (pintype "power_in"))
      (node (ref "U$25") (pin "P$4") (pinfunction "VO-_P$4") (pintype "power_in"))
      (node (ref "U$8") (pin "2") (pinfunction "GND_2_2") (pintype "power_in"))
      (node (ref "U$8") (pin "3") (pinfunction "GND_3_3") (pintype "power_in"))
      (node (ref "U$8") (pin "4") (pinfunction "LIN4_4") (pintype "input"))
      (node (ref "U$8") (pin "5") (pinfunction "LOUT5_5") (pintype "input"))
      (node (ref "U$8") (pin "6") (pinfunction "GND_6_6") (pintype "power_in"))
      (node (ref "U$8") (pin "7") (pinfunction "GND_7_7") (pintype "power_in"))
    )
    (net (code "14") (name "/NRST") (class "Default")
      (node (ref "JP9") (pin "3") (pinfunction "3_3") (pintype "passive"))
      (node (ref "R21") (pin "2") (pinfunction "2_2") (pintype "passive"))
    )
    (net (code "15") (name "/PA3") (class "Default")
      (node (ref "JP10") (pin "2") (pinfunction "2_2") (pintype "passive"))
      (node (ref "R26") (pin "2") (pinfunction "2_2") (pintype "passive"))
    )
    (net (code "16") (name "/PA4") (class "Default")
      (node (ref "JP10") (pin "4") (pinfunction "4_4") (pintype "passive"))
      (node (ref "R25") (pin "2") (pinfunction "2_2") (pintype "passive"))
    )
    (net (code "17") (name "/PA5") (class "Default")
      (node (ref "JP10") (pin "5") (pinfunction "5_5") (pintype "passive"))
      (node (ref "R24") (pin "2") (pinfunction "2_2") (pintype "passive"))
    )
    (net (code "18") (name "/PA6") (class "Default")
      (node (ref "JP9") (pin "1") (pinfunction "1_1") (pintype "passive"))
      (node (ref "R23") (pin "2") (pinfunction "2_2") (pintype "passive"))
    )
    (net (code "19") (name "/PA7") (class "Default")
      (node (ref "JP9") (pin "2") (pinfunction "2_2") (pintype "passive"))
      (node (ref "R22") (pin "2") (pinfunction "2_2") (pintype "passive"))
    )
    (net (code "20") (name "/PB0") (class "Default")
      (node (ref "JP10") (pin "3") (pinfunction "3_3") (pintype "passive"))
      (node (ref "R32") (pin "2") (pinfunction "2_2") (pintype "passive"))
    )
    (net (code "21") (name "/VCCA") (class "Default")
      (node (ref "C2") (pin "1") (pinfunction "1_1") (pintype "passive"))
      (node (ref "C29") (pin "2") (pinfunction "P$2_2") (pintype "passive"))
      (node (ref "R40") (pin "1") (pinfunction "1_1") (pintype "passive"))
      (node (ref "R42") (pin "1") (pinfunction "1_1") (pintype "passive"))
      (node (ref "R46") (pin "1") (pinfunction "1_1") (pintype "passive"))
      (node (ref "U$17") (pin "P$5") (pinfunction "VO+_P$5") (pintype "power_in"))
      (node (ref "U$2") (pin "P$1") (pinfunction "VDD1_P$1") (pintype "power_in"))
    )
    (net (code "22") (name "/VCCB") (class "Default")
      (node (ref "C30") (pin "2") (pinfunction "P$2_2") (pintype "passive"))
      (node (ref "C7") (pin "1") (pinfunction "1_1") (pintype "passive"))
      (node (ref "R47") (pin "1") (pinfunction "1_1") (pintype "passive"))
      (node (ref "R48") (pin "1") (pinfunction "1_1") (pintype "passive"))
      (node (ref "R51") (pin "1") (pinfunction "1_1") (pintype "passive"))
      (node (ref "U$20") (pin "P$5") (pinfunction "VO+_P$5") (pintype "power_in"))
      (node (ref "U$9") (pin "P$1") (pinfunction "VDD1_P$1") (pintype "power_in"))
    )
    (net (code "23") (name "/VCCC") (class "Default")
      (node (ref "C31") (pin "2") (pinfunction "P$2_2") (pintype "passive"))
      (node (ref "C9") (pin "1") (pinfunction "1_1") (pintype "passive"))
      (node (ref "R52") (pin "1") (pinfunction "1_1") (pintype "passive"))
      (node (ref "R53") (pin "1") (pinfunction "1_1") (pintype "passive"))
      (node (ref "R55") (pin "1") (pinfunction "1_1") (pintype "passive"))
      (node (ref "U$12") (pin "P$1") (pinfunction "VDD1_P$1") (pintype "power_in"))
      (node (ref "U$22") (pin "P$5") (pinfunction "VO+_P$5") (pintype "power_in"))
    )
    (net (code "24") (name "/VCCD") (class "Default")
      (node (ref "C11") (pin "1") (pinfunction "1_1") (pintype "passive"))
      (node (ref "C32") (pin "2") (pinfunction "P$2_2") (pintype "passive"))
      (node (ref "R56") (pin "1") (pinfunction "1_1") (pintype "passive"))
      (node (ref "R57") (pin "1") (pinfunction "1_1") (pintype "passive"))
      (node (ref "R59") (pin "1") (pinfunction "1_1") (pintype "passive"))
      (node (ref "U$16") (pin "P$1") (pinfunction "VDD1_P$1") (pintype "power_in"))
      (node (ref "U$23") (pin "P$5") (pinfunction "VO+_P$5") (pintype "power_in"))
    )
    (net (code "25") (name "/VCCE") (class "Default")
      (node (ref "C12") (pin "1") (pinfunction "1_1") (pintype "passive"))
      (node (ref "C33") (pin "2") (pinfunction "P$2_2") (pintype "passive"))
      (node (ref "R60") (pin "1") (pinfunction "1_1") (pintype "passive"))
      (node (ref "R61") (pin "1") (pinfunction "1_1") (pintype "passive"))
      (node (ref "R63") (pin "1") (pinfunction "1_1") (pintype "passive"))
      (node (ref "U$18") (pin "P$1") (pinfunction "VDD1_P$1") (pintype "power_in"))
      (node (ref "U$24") (pin "P$5") (pinfunction "VO+_P$5") (pintype "power_in"))
    )
    (net (code "26") (name "/VCCF") (class "Default")
      (node (ref "C13") (pin "1") (pinfunction "1_1") (pintype "passive"))
      (node (ref "C36") (pin "2") (pinfunction "P$2_2") (pintype "passive"))
      (node (ref "R64") (pin "1") (pinfunction "1_1") (pintype "passive"))
      (node (ref "R65") (pin "1") (pinfunction "1_1") (pintype "passive"))
      (node (ref "R67") (pin "1") (pinfunction "1_1") (pintype "passive"))
      (node (ref "U$19") (pin "P$1") (pinfunction "VDD1_P$1") (pintype "power_in"))
      (node (ref "U$25") (pin "P$5") (pinfunction "VO+_P$5") (pintype "power_in"))
    )
    (net (code "27") (name "3.3V") (class "Default")
      (node (ref "C6") (pin "2") (pinfunction "P$2_2") (pintype "passive"))
      (node (ref "JP9") (pin "4") (pinfunction "4_4") (pintype "passive"))
      (node (ref "R20") (pin "2") (pinfunction "2_2") (pintype "passive"))
    )
    (net (code "28") (name "5V") (class "Default")
      (node (ref "C35") (pin "1") (pinfunction "P$1_1") (pintype "passive"))
      (node (ref "C37") (pin "1") (pinfunction "P$1_1") (pintype "passive"))
      (node (ref "C38") (pin "1") (pinfunction "P$1_1") (pintype "passive"))
      (node (ref "C39") (pin "1") (pinfunction "P$1_1") (pintype "passive"))
      (node (ref "C40") (pin "1") (pinfunction "P$1_1") (pintype "passive"))
      (node (ref "C41") (pin "1") (pinfunction "P$1_1") (pintype "passive"))
      (node (ref "C42") (pin "1") (pinfunction "P$1_1") (pintype "passive"))
      (node (ref "JP9") (pin "5") (pinfunction "5_5") (pintype "passive"))
      (node (ref "L1") (pin "2") (pinfunction "2_2") (pintype "passive"))
      (node (ref "U$12") (pin "P$8") (pinfunction "VDD2_P$8") (pintype "power_in"))
      (node (ref "U$16") (pin "P$8") (pinfunction "VDD2_P$8") (pintype "power_in"))
      (node (ref "U$18") (pin "P$8") (pinfunction "VDD2_P$8") (pintype "power_in"))
      (node (ref "U$19") (pin "P$8") (pinfunction "VDD2_P$8") (pintype "power_in"))
      (node (ref "U$2") (pin "P$8") (pinfunction "VDD2_P$8") (pintype "power_in"))
      (node (ref "U$9") (pin "P$8") (pinfunction "VDD2_P$8") (pintype "power_in"))
    )
    (net (code "29") (name "AGND") (class "Default")
      (node (ref ".") (pin "P$11") (pinfunction "CH4-_P$11") (pintype "bidirectional"))
      (node (ref ".") (pin "P$12") (pinfunction "CH5-_P$12") (pintype "bidirectional"))
      (node (ref ".") (pin "P$15") (pinfunction "REFIN-_P$15") (pintype "bidirectional"))
      (node (ref ".") (pin "P$16") (pinfunction "AGND_P$16") (pintype "bidirectional"))
      (node (ref ".") (pin "P$17") (pinfunction "DGND_P$17") (pintype "bidirectional"))
      (node (ref ".") (pin "P$22") (pinfunction "OSC2_P$22") (pintype "bidirectional"))
      (node (ref ".") (pin "P$3") (pinfunction "CH0-_P$3") (pintype "bidirectional"))
      (node (ref ".") (pin "P$4") (pinfunction "CH1-_P$4") (pintype "bidirectional"))
      (node (ref ".") (pin "P$7") (pinfunction "CH2-_P$7") (pintype "bidirectional"))
      (node (ref ".") (pin "P$8") (pinfunction "CH3-_P$8") (pintype "bidirectional"))
      (node (ref "C1") (pin "2") (pinfunction "P$2_2") (pintype "passive"))
      (node (ref "C10") (pin "2") (pinfunction "2_2") (pintype "passive"))
      (node (ref "C14") (pin "2") (pinfunction "2_2") (pintype "passive"))
      (node (ref "C15") (pin "2") (pinfunction "2_2") (pintype "passive"))
      (node (ref "C16") (pin "2") (pinfunction "2_2") (pintype "passive"))
      (node (ref "C17") (pin "2") (pinfunction "2_2") (pintype "passive"))
      (node (ref "C18") (pin "2") (pinfunction "2_2") (pintype "passive"))
      (node (ref "C19") (pin "1") (pinfunction "P$1_1") (pintype "passive"))
      (node (ref "C20") (pin "2") (pinfunction "2_2") (pintype "passive"))
      (node (ref "C21") (pin "2") (pinfunction "P$2_2") (pintype "passive"))
      (node (ref "C22") (pin "2") (pinfunction "P$2_2") (pintype "passive"))
      (node (ref "C23") (pin "2") (pinfunction "P$2_2") (pintype "passive"))
      (node (ref "C24") (pin "2") (pinfunction "2_2") (pintype "passive"))
      (node (ref "C25") (pin "2") (pinfunction "P$2_2") (pintype "passive"))
      (node (ref "C26") (pin "2") (pinfunction "2_2") (pintype "passive"))
      (node (ref "C27") (pin "2") (pinfunction "2_2") (pintype "passive"))
      (node (ref "C28") (pin "2") (pinfunction "P$2_2") (pintype "passive"))
      (node (ref "C3") (pin "2") (pinfunction "P$2_2") (pintype "passive"))
      (node (ref "C34") (pin "2") (pinfunction "P$2_2") (pintype "passive"))
      (node (ref "C35") (pin "2") (pinfunction "P$2_2") (pintype "passive"))
      (node (ref "C37") (pin "2") (pinfunction "P$2_2") (pintype "passive"))
      (node (ref "C38") (pin "2") (pinfunction "P$2_2") (pintype "passive"))
      (node (ref "C39") (pin "2") (pinfunction "P$2_2") (pintype "passive"))
      (node (ref "C4") (pin "2") (pinfunction "2_2") (pintype "passive"))
      (node (ref "C40") (pin "2") (pinfunction "P$2_2") (pintype "passive"))
      (node (ref "C41") (pin "2") (pinfunction "P$2_2") (pintype "passive"))
      (node (ref "C42") (pin "2") (pinfunction "P$2_2") (pintype "passive"))
      (node (ref "C5") (pin "2") (pinfunction "P$2_2") (pintype "passive"))
      (node (ref "C6") (pin "1") (pinfunction "P$1_1") (pintype "passive"))
      (node (ref "C8") (pin "2") (pinfunction "2_2") (pintype "passive"))
      (node (ref "JP1") (pin "2") (pinfunction "2_2") (pintype "passive"))
      (node (ref "JP10") (pin "1") (pinfunction "1_1") (pintype "passive"))
      (node (ref "U$12") (pin "P$5") (pinfunction "GND2_P$5") (pintype "power_in"))
      (node (ref "U$12") (pin "P$6") (pinfunction "VOUT-_P$6") (pintype "bidirectional"))
      (node (ref "U$16") (pin "P$5") (pinfunction "GND2_P$5") (pintype "power_in"))
      (node (ref "U$16") (pin "P$6") (pinfunction "VOUT-_P$6") (pintype "bidirectional"))
      (node (ref "U$17") (pin "P$1") (pinfunction "VIN-_P$1") (pintype "power_in"))
      (node (ref "U$18") (pin "P$5") (pinfunction "GND2_P$5") (pintype "power_in"))
      (node (ref "U$18") (pin "P$6") (pinfunction "VOUT-_P$6") (pintype "bidirectional"))
      (node (ref "U$19") (pin "P$5") (pinfunction "GND2_P$5") (pintype "power_in"))
      (node (ref "U$19") (pin "P$6") (pinfunction "VOUT-_P$6") (pintype "bidirectional"))
      (node (ref "U$2") (pin "P$5") (pinfunction "GND2_P$5") (pintype "power_in"))
      (node (ref "U$2") (pin "P$6") (pinfunction "VOUT-_P$6") (pintype "bidirectional"))
      (node (ref "U$20") (pin "P$1") (pinfunction "VIN-_P$1") (pintype "power_in"))
      (node (ref "U$22") (pin "P$1") (pinfunction "VIN-_P$1") (pintype "power_in"))
      (node (ref "U$23") (pin "P$1") (pinfunction "VIN-_P$1") (pintype "power_in"))
      (node (ref "U$24") (pin "P$1") (pinfunction "VIN-_P$1") (pintype "power_in"))
      (node (ref "U$25") (pin "P$1") (pinfunction "VIN-_P$1") (pintype "power_in"))
      (node (ref "U$9") (pin "P$5") (pinfunction "GND2_P$5") (pintype "power_in"))
      (node (ref "U$9") (pin "P$6") (pinfunction "VOUT-_P$6") (pintype "bidirectional"))
    )
    (net (code "30") (name "Net-(.-AVDD)") (class "Default")
      (node (ref ".") (pin "P$1") (pinfunction "AVDD_P$1") (pintype "bidirectional"))
      (node (ref "C19") (pin "2") (pinfunction "P$2_2") (pintype "passive"))
      (node (ref "R19") (pin "1") (pinfunction "1_1") (pintype "passive"))
    )
    (net (code "31") (name "Net-(.-DVDD)") (class "Default")
      (node (ref ".") (pin "P$28") (pinfunction "DVDD_P$28") (pintype "bidirectional"))
      (node (ref "C21") (pin "1") (pinfunction "P$1_1") (pintype "passive"))
      (node (ref "R20") (pin "1") (pinfunction "1_1") (pintype "passive"))
    )
    (net (code "32") (name "Net-(.-OSC1)") (class "Default")
      (node (ref ".") (pin "P$21") (pinfunction "OSC1_P$21") (pintype "bidirectional"))
      (node (ref "R32") (pin "1") (pinfunction "1_1") (pintype "passive"))
    )
    (net (code "33") (name "Net-(.-REFIN{slash}OUT)") (class "Default")
      (node (ref ".") (pin "P$14") (pinfunction "REFIN/OUT_P$14") (pintype "bidirectional"))
      (node (ref "C22") (pin "1") (pinfunction "P$1_1") (pintype "passive"))
    )
    (net (code "34") (name "Net-(.-SCK)") (class "Default")
      (node (ref ".") (pin "P$24") (pinfunction "SCK_P$24") (pintype "bidirectional"))
      (node (ref "R24") (pin "1") (pinfunction "1_1") (pintype "passive"))
    )
    (net (code "35") (name "Net-(.-SDI)") (class "Default")
      (node (ref ".") (pin "P$26") (pinfunction "SDI_P$26") (pintype "bidirectional"))
      (node (ref "R22") (pin "1") (pinfunction "1_1") (pintype "passive"))
    )
    (net (code "36") (name "Net-(.-SDO)") (class "Default")
      (node (ref ".") (pin "P$25") (pinfunction "SDO_P$25") (pintype "bidirectional"))
      (node (ref "R23") (pin "1") (pinfunction "1_1") (pintype "passive"))
    )
    (net (code "37") (name "Net-(.-{slash}CS)") (class "Default")
      (node (ref ".") (pin "P$23") (pinfunction "/CS_P$23") (pintype "bidirectional"))
      (node (ref "R25") (pin "1") (pinfunction "1_1") (pintype "passive"))
    )
    (net (code "38") (name "Net-(.-{slash}DRA)") (class "Default")
      (node (ref ".") (pin "P$18") (pinfunction "/DRA_P$18") (pintype "bidirectional"))
      (node (ref "R26") (pin "1") (pinfunction "1_1") (pintype "passive"))
    )
    (net (code "39") (name "Net-(.-{slash}RESET)") (class "Default")
      (node (ref ".") (pin "P$27") (pinfunction "/RESET_P$27") (pintype "bidirectional"))
      (node (ref "R21") (pin "1") (pinfunction "1_1") (pintype "passive"))
    )
    (net (code "40") (name "Net-(C34-P$1)") (class "Default")
      (node (ref "C34") (pin "1") (pinfunction "P$1_1") (pintype "passive"))
      (node (ref "L1") (pin "1") (pinfunction "1_1") (pintype "passive"))
      (node (ref "R19") (pin "2") (pinfunction "2_2") (pintype "passive"))
    )
    (net (code "41") (name "Net-(D1-PadA)") (class "Default")
      (node (ref "D1") (pin "A") (pinfunction "A_A") (pintype "passive"))
      (node (ref "R46") (pin "2") (pinfunction "2_2") (pintype "passive"))
    )
    (net (code "42") (name "Net-(D2-PadA)") (class "Default")
      (node (ref "D2") (pin "A") (pinfunction "A_A") (pintype "passive"))
      (node (ref "JP1") (pin "1") (pinfunction "1_1") (pintype "passive"))
    )
    (net (code "43") (name "Net-(D3-PadA)") (class "Default")
      (node (ref "D3") (pin "A") (pinfunction "A_A") (pintype "passive"))
      (node (ref "R51") (pin "2") (pinfunction "2_2") (pintype "passive"))
    )
    (net (code "44") (name "Net-(D4-PadA)") (class "Default")
      (node (ref "D4") (pin "A") (pinfunction "A_A") (pintype "passive"))
      (node (ref "R55") (pin "2") (pinfunction "2_2") (pintype "passive"))
    )
    (net (code "45") (name "Net-(D5-PadA)") (class "Default")
      (node (ref "D5") (pin "A") (pinfunction "A_A") (pintype "passive"))
      (node (ref "R59") (pin "2") (pinfunction "2_2") (pintype "passive"))
    )
    (net (code "46") (name "Net-(D6-PadA)") (class "Default")
      (node (ref "D6") (pin "A") (pinfunction "A_A") (pintype "passive"))
      (node (ref "R63") (pin "2") (pinfunction "2_2") (pintype "passive"))
    )
    (net (code "47") (name "Net-(D7-PadA)") (class "Default")
      (node (ref "D7") (pin "A") (pinfunction "A_A") (pintype "passive"))
      (node (ref "R67") (pin "2") (pinfunction "2_2") (pintype "passive"))
    )
    (net (code "48") (name "Net-(Q1-B)") (class "Default")
      (node (ref "Q1") (pin "1") (pinfunction "B_1") (pintype "passive"))
      (node (ref "R42") (pin "2") (pinfunction "2_2") (pintype "passive"))
      (node (ref "R44") (pin "1") (pinfunction "1_1") (pintype "passive"))
    )
    (net (code "49") (name "Net-(Q1-E)") (class "Default")
      (node (ref "Q1") (pin "2") (pinfunction "E_2") (pintype "passive"))
      (node (ref "R40") (pin "2") (pinfunction "2_2") (pintype "passive"))
    )
    (net (code "50") (name "Net-(Q3-B)") (class "Default")
      (node (ref "Q3") (pin "1") (pinfunction "B_1") (pintype "passive"))
      (node (ref "R48") (pin "2") (pinfunction "2_2") (pintype "passive"))
      (node (ref "R49") (pin "1") (pinfunction "1_1") (pintype "passive"))
    )
    (net (code "51") (name "Net-(Q3-E)") (class "Default")
      (node (ref "Q3") (pin "2") (pinfunction "E_2") (pintype "passive"))
      (node (ref "R47") (pin "2") (pinfunction "2_2") (pintype "passive"))
    )
    (net (code "52") (name "Net-(Q4-B)") (class "Default")
      (node (ref "Q4") (pin "1") (pinfunction "B_1") (pintype "passive"))
      (node (ref "R53") (pin "2") (pinfunction "2_2") (pintype "passive"))
      (node (ref "R54") (pin "1") (pinfunction "1_1") (pintype "passive"))
    )
    (net (code "53") (name "Net-(Q4-E)") (class "Default")
      (node (ref "Q4") (pin "2") (pinfunction "E_2") (pintype "passive"))
      (node (ref "R52") (pin "2") (pinfunction "2_2") (pintype "passive"))
    )
    (net (code "54") (name "Net-(Q5-B)") (class "Default")
      (node (ref "Q5") (pin "1") (pinfunction "B_1") (pintype "passive"))
      (node (ref "R57") (pin "2") (pinfunction "2_2") (pintype "passive"))
      (node (ref "R58") (pin "1") (pinfunction "1_1") (pintype "passive"))
    )
    (net (code "55") (name "Net-(Q5-E)") (class "Default")
      (node (ref "Q5") (pin "2") (pinfunction "E_2") (pintype "passive"))
      (node (ref "R56") (pin "2") (pinfunction "2_2") (pintype "passive"))
    )
    (net (code "56") (name "Net-(Q6-B)") (class "Default")
      (node (ref "Q6") (pin "1") (pinfunction "B_1") (pintype "passive"))
      (node (ref "R61") (pin "2") (pinfunction "2_2") (pintype "passive"))
      (node (ref "R62") (pin "1") (pinfunction "1_1") (pintype "passive"))
    )
    (net (code "57") (name "Net-(Q6-E)") (class "Default")
      (node (ref "Q6") (pin "2") (pinfunction "E_2") (pintype "passive"))
      (node (ref "R60") (pin "2") (pinfunction "2_2") (pintype "passive"))
    )
    (net (code "58") (name "Net-(Q7-B)") (class "Default")
      (node (ref "Q7") (pin "1") (pinfunction "B_1") (pintype "passive"))
      (node (ref "R65") (pin "2") (pinfunction "2_2") (pintype "passive"))
      (node (ref "R66") (pin "1") (pinfunction "1_1") (pintype "passive"))
    )
    (net (code "59") (name "Net-(Q7-E)") (class "Default")
      (node (ref "Q7") (pin "2") (pinfunction "E_2") (pintype "passive"))
      (node (ref "R64") (pin "2") (pinfunction "2_2") (pintype "passive"))
    )
    (net (code "60") (name "Net-(U$2-VIN+)") (class "Default")
      (node (ref "R1") (pin "1") (pinfunction "1_1") (pintype "passive"))
      (node (ref "R3") (pin "2") (pinfunction "2_2") (pintype "passive"))
      (node (ref "U$2") (pin "P$2") (pinfunction "VIN+_P$2") (pintype "bidirectional"))
    )
    (net (code "61") (name "Net-(U$2-VOUT+)") (class "Default")
      (node (ref "R35") (pin "1") (pinfunction "1_1") (pintype "passive"))
      (node (ref "U$2") (pin "P$7") (pinfunction "VOUT+_P$7") (pintype "bidirectional"))
    )
    (net (code "62") (name "Net-(U$3-LIN1)") (class "Default")
      (node (ref "JP11") (pin "2") (pinfunction "2_2") (pintype "passive"))
      (node (ref "R1") (pin "2") (pinfunction "2_2") (pintype "passive"))
      (node (ref "R13") (pin "1") (pinfunction "1_1") (pintype "passive"))
      (node (ref "R28") (pin "1") (pinfunction "1_1") (pintype "passive"))
      (node (ref "U$3") (pin "1") (pinfunction "LIN1_1") (pintype "input"))
      (node (ref "U$3") (pin "8") (pinfunction "LOUT8_8") (pintype "bidirectional"))
    )
    (net (code "63") (name "Net-(U$4-LIN1)") (class "Default")
      (node (ref "JP8") (pin "1") (pinfunction "1_1") (pintype "passive"))
      (node (ref "R14") (pin "1") (pinfunction "1_1") (pintype "passive"))
      (node (ref "R29") (pin "1") (pinfunction "1_1") (pintype "passive"))
      (node (ref "R4") (pin "2") (pinfunction "2_2") (pintype "passive"))
      (node (ref "U$4") (pin "1") (pinfunction "LIN1_1") (pintype "input"))
      (node (ref "U$4") (pin "8") (pinfunction "LOUT8_8") (pintype "bidirectional"))
    )
    (net (code "64") (name "Net-(U$5-LIN1)") (class "Default")
      (node (ref "JP3") (pin "2") (pinfunction "2_2") (pintype "passive"))
      (node (ref "R15") (pin "1") (pinfunction "1_1") (pintype "passive"))
      (node (ref "R30") (pin "1") (pinfunction "1_1") (pintype "passive"))
      (node (ref "R7") (pin "2") (pinfunction "2_2") (pintype "passive"))
      (node (ref "U$5") (pin "1") (pinfunction "LIN1_1") (pintype "input"))
      (node (ref "U$5") (pin "8") (pinfunction "LOUT8_8") (pintype "bidirectional"))
    )
    (net (code "65") (name "Net-(U$6-LIN1)") (class "Default")
      (node (ref "JP4") (pin "1") (pinfunction "1_1") (pintype "passive"))
      (node (ref "R10") (pin "2") (pinfunction "2_2") (pintype "passive"))
      (node (ref "R16") (pin "1") (pinfunction "1_1") (pintype "passive"))
      (node (ref "R31") (pin "1") (pinfunction "1_1") (pintype "passive"))
      (node (ref "U$6") (pin "1") (pinfunction "LIN1_1") (pintype "input"))
      (node (ref "U$6") (pin "8") (pinfunction "LOUT8_8") (pintype "bidirectional"))
    )
    (net (code "66") (name "Net-(U$7-LIN1)") (class "Default")
      (node (ref "JP6") (pin "2") (pinfunction "2_2") (pintype "passive"))
      (node (ref "R12") (pin "2") (pinfunction "2_2") (pintype "passive"))
      (node (ref "R17") (pin "1") (pinfunction "1_1") (pintype "passive"))
      (node (ref "R33") (pin "1") (pinfunction "1_1") (pintype "passive"))
      (node (ref "U$7") (pin "1") (pinfunction "LIN1_1") (pintype "input"))
      (node (ref "U$7") (pin "8") (pinfunction "LOUT8_8") (pintype "bidirectional"))
    )
    (net (code "67") (name "Net-(U$8-LIN1)") (class "Default")
      (node (ref "JP7") (pin "1") (pinfunction "1_1") (pintype "passive"))
      (node (ref "R18") (pin "1") (pinfunction "1_1") (pintype "passive"))
      (node (ref "R34") (pin "1") (pinfunction "1_1") (pintype "passive"))
      (node (ref "R36") (pin "2") (pinfunction "2_2") (pintype "passive"))
      (node (ref "U$8") (pin "1") (pinfunction "LIN1_1") (pintype "input"))
      (node (ref "U$8") (pin "8") (pinfunction "LOUT8_8") (pintype "bidirectional"))
    )
    (net (code "68") (name "Net-(U$9-VIN+)") (class "Default")
      (node (ref "R4") (pin "1") (pinfunction "1_1") (pintype "passive"))
      (node (ref "R5") (pin "1") (pinfunction "1_1") (pintype "passive"))
      (node (ref "U$9") (pin "P$2") (pinfunction "VIN+_P$2") (pintype "bidirectional"))
    )
    (net (code "69") (name "Net-(U$9-VOUT+)") (class "Default")
      (node (ref "R37") (pin "1") (pinfunction "1_1") (pintype "passive"))
      (node (ref "U$9") (pin "P$7") (pinfunction "VOUT+_P$7") (pintype "bidirectional"))
    )
    (net (code "70") (name "Net-(U$12-VIN+)") (class "Default")
      (node (ref "R7") (pin "1") (pinfunction "1_1") (pintype "passive"))
      (node (ref "R9") (pin "1") (pinfunction "1_1") (pintype "passive"))
      (node (ref "U$12") (pin "P$2") (pinfunction "VIN+_P$2") (pintype "bidirectional"))
    )
    (net (code "71") (name "Net-(U$12-VOUT+)") (class "Default")
      (node (ref "R39") (pin "1") (pinfunction "1_1") (pintype "passive"))
      (node (ref "U$12") (pin "P$7") (pinfunction "VOUT+_P$7") (pintype "bidirectional"))
    )
    (net (code "72") (name "Net-(U$16-VIN+)") (class "Default")
      (node (ref "R10") (pin "1") (pinfunction "1_1") (pintype "passive"))
      (node (ref "R11") (pin "1") (pinfunction "1_1") (pintype "passive"))
      (node (ref "U$16") (pin "P$2") (pinfunction "VIN+_P$2") (pintype "bidirectional"))
    )
    (net (code "73") (name "Net-(U$16-VOUT+)") (class "Default")
      (node (ref "R41") (pin "1") (pinfunction "1_1") (pintype "passive"))
      (node (ref "U$16") (pin "P$7") (pinfunction "VOUT+_P$7") (pintype "bidirectional"))
    )
    (net (code "74") (name "Net-(U$17-VIN+)") (class "Default")
      (node (ref "C10") (pin "1") (pinfunction "1_1") (pintype "passive"))
      (node (ref "L2") (pin "1") (pinfunction "1_1") (pintype "passive"))
      (node (ref "U$17") (pin "P$2") (pinfunction "VIN+_P$2") (pintype "power_in"))
    )
    (net (code "75") (name "Net-(U$18-VIN+)") (class "Default")
      (node (ref "R12") (pin "1") (pinfunction "1_1") (pintype "passive"))
      (node (ref "R27") (pin "1") (pinfunction "1_1") (pintype "passive"))
      (node (ref "U$18") (pin "P$2") (pinfunction "VIN+_P$2") (pintype "bidirectional"))
    )
    (net (code "76") (name "Net-(U$18-VOUT+)") (class "Default")
      (node (ref "R43") (pin "1") (pinfunction "1_1") (pintype "passive"))
      (node (ref "U$18") (pin "P$7") (pinfunction "VOUT+_P$7") (pintype "bidirectional"))
    )
    (net (code "77") (name "Net-(U$19-VIN+)") (class "Default")
      (node (ref "R36") (pin "1") (pinfunction "1_1") (pintype "passive"))
      (node (ref "R38") (pin "1") (pinfunction "1_1") (pintype "passive"))
      (node (ref "U$19") (pin "P$2") (pinfunction "VIN+_P$2") (pintype "bidirectional"))
    )
    (net (code "78") (name "Net-(U$19-VOUT+)") (class "Default")
      (node (ref "R45") (pin "1") (pinfunction "1_1") (pintype "passive"))
      (node (ref "U$19") (pin "P$7") (pinfunction "VOUT+_P$7") (pintype "bidirectional"))
    )
    (net (code "79") (name "Net-(U$20-VIN+)") (class "Default")
      (node (ref "C14") (pin "1") (pinfunction "1_1") (pintype "passive"))
      (node (ref "L3") (pin "1") (pinfunction "1_1") (pintype "passive"))
      (node (ref "U$20") (pin "P$2") (pinfunction "VIN+_P$2") (pintype "power_in"))
    )
    (net (code "80") (name "Net-(U$22-VIN+)") (class "Default")
      (node (ref "C16") (pin "1") (pinfunction "1_1") (pintype "passive"))
      (node (ref "L4") (pin "1") (pinfunction "1_1") (pintype "passive"))
      (node (ref "U$22") (pin "P$2") (pinfunction "VIN+_P$2") (pintype "power_in"))
    )
    (net (code "81") (name "Net-(U$23-VIN+)") (class "Default")
      (node (ref "C18") (pin "1") (pinfunction "1_1") (pintype "passive"))
      (node (ref "L5") (pin "1") (pinfunction "1_1") (pintype "passive"))
      (node (ref "U$23") (pin "P$2") (pinfunction "VIN+_P$2") (pintype "power_in"))
    )
    (net (code "82") (name "Net-(U$24-VIN+)") (class "Default")
      (node (ref "C24") (pin "1") (pinfunction "1_1") (pintype "passive"))
      (node (ref "L6") (pin "1") (pinfunction "1_1") (pintype "passive"))
      (node (ref "U$24") (pin "P$2") (pinfunction "VIN+_P$2") (pintype "power_in"))
    )
    (net (code "83") (name "Net-(U$25-VIN+)") (class "Default")
      (node (ref "C27") (pin "1") (pinfunction "1_1") (pintype "passive"))
      (node (ref "L7") (pin "1") (pinfunction "1_1") (pintype "passive"))
      (node (ref "U$25") (pin "P$2") (pinfunction "VIN+_P$2") (pintype "power_in"))
    )
    (net (code "84") (name "unconnected-(.-{slash}DRB-PadP$19)") (class "Default")
      (node (ref ".") (pin "P$19") (pinfunction "/DRB_P$19") (pintype "bidirectional"))
    )
    (net (code "85") (name "unconnected-(.-{slash}DRC-PadP$20)") (class "Default")
      (node (ref ".") (pin "P$20") (pinfunction "/DRC_P$20") (pintype "bidirectional"))
    )
    (net (code "86") (name "unconnected-(JP2-Pad1)") (class "Default")
      (node (ref "JP2") (pin "1") (pinfunction "1_1") (pintype "passive"))
    )
    (net (code "87") (name "unconnected-(JP4-Pad2)") (class "Default")
      (node (ref "JP4") (pin "2") (pinfunction "2_2") (pintype "passive"))
    )
    (net (code "88") (name "unconnected-(JP5-Pad1)") (class "Default")
      (node (ref "JP5") (pin "1") (pinfunction "1_1") (pintype "passive"))
    )
    (net (code "89") (name "unconnected-(JP7-Pad2)") (class "Default")
      (node (ref "JP7") (pin "2") (pinfunction "2_2") (pintype "passive"))
    )
    (net (code "90") (name "unconnected-(JP8-Pad2)") (class "Default")
      (node (ref "JP8") (pin "2") (pinfunction "2_2") (pintype "passive"))
    )
    (net (code "91") (name "unconnected-(JP12-Pad1)") (class "Default")
      (node (ref "JP12") (pin "1") (pinfunction "1_1") (pintype "passive"))
    )
    (net (code "92") (name "unconnected-(U$17-PadP$8)") (class "Default")
      (node (ref "U$17") (pin "P$8") (pinfunction "P$8_P$8") (pintype "no_connect"))
    )
    (net (code "93") (name "unconnected-(U$20-PadP$8)") (class "Default")
      (node (ref "U$20") (pin "P$8") (pinfunction "P$8_P$8") (pintype "no_connect"))
    )
    (net (code "94") (name "unconnected-(U$22-PadP$8)") (class "Default")
      (node (ref "U$22") (pin "P$8") (pinfunction "P$8_P$8") (pintype "no_connect"))
    )
    (net (code "95") (name "unconnected-(U$23-PadP$8)") (class "Default")
      (node (ref "U$23") (pin "P$8") (pinfunction "P$8_P$8") (pintype "no_connect"))
    )
    (net (code "96") (name "unconnected-(U$24-PadP$8)") (class "Default")
      (node (ref "U$24") (pin "P$8") (pinfunction "P$8_P$8") (pintype "no_connect"))
    )
    (net (code "97") (name "unconnected-(U$25-PadP$8)") (class "Default")
      (node (ref "U$25") (pin "P$8") (pinfunction "P$8_P$8") (pintype "no_connect"))
    )
  )
)
